# IambicKey.net
KiCad netlist of a schematic drawn in EAGLE
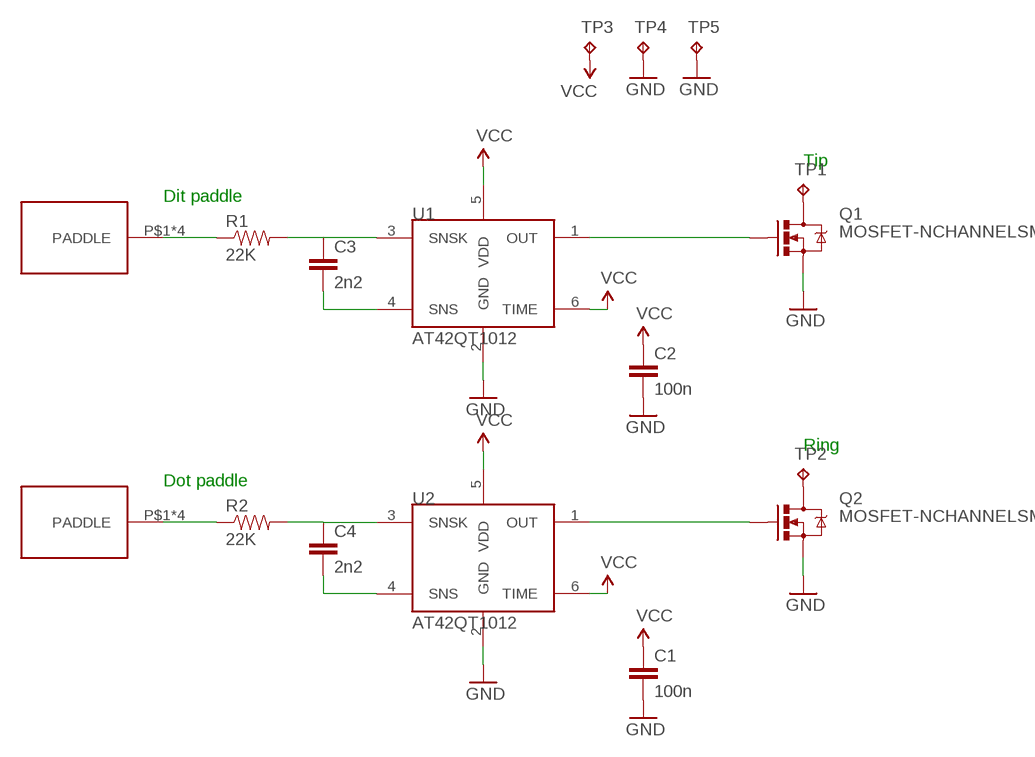
[diagram p0: schematic, sheet 1]

(export (version "E")
  (design (tool "Eeschema 10.0.6"))
  (components
    (comp (ref "C1")
      (value "100n")
      (footprint "eagle-import:0603-CAP")
      (libsource (lib "eagle-import") (part "CAP0603-CAP"))
    )
    (comp (ref "C2")
      (value "100n")
      (footprint "eagle-import:0603-CAP")
      (libsource (lib "eagle-import") (part "CAP0603-CAP"))
    )
    (comp (ref "C3")
      (value "2n2")
      (footprint "eagle-import:0603-CAP")
      (libsource (lib "eagle-import") (part "CAP0603-CAP"))
    )
    (comp (ref "C4")
      (value "2n2")
      (footprint "eagle-import:0603-CAP")
      (libsource (lib "eagle-import") (part "CAP0603-CAP"))
    )
    (comp (ref "Q1")
      (value "MOSFET-NCHANNELSMD")
      (footprint "eagle-import:SOT23-3")
      (libsource (lib "eagle-import") (part "MOSFET-NCHANNELSMD"))
    )
    (comp (ref "Q2")
      (value "MOSFET-NCHANNELSMD")
      (footprint "eagle-import:SOT23-3")
      (libsource (lib "eagle-import") (part "MOSFET-NCHANNELSMD"))
    )
    (comp (ref "R1")
      (value "22K")
      (footprint "eagle-import:0603-RES")
      (libsource (lib "eagle-import") (part "RESISTOR0603-RES"))
    )
    (comp (ref "R2")
      (value "22K")
      (footprint "eagle-import:0603-RES")
      (libsource (lib "eagle-import") (part "RESISTOR0603-RES"))
    )
    (comp (ref "TP1")
      (value "TPTP20SQ")
      (footprint "eagle-import:TP20SQ")
      (libsource (lib "eagle-import") (part "TPTP20SQ"))
    )
    (comp (ref "TP2")
      (value "TPTP20SQ")
      (footprint "eagle-import:TP20SQ")
      (libsource (lib "eagle-import") (part "TPTP20SQ"))
    )
    (comp (ref "TP3")
      (value "TPTP20SQ")
      (footprint "eagle-import:TP20SQ")
      (libsource (lib "eagle-import") (part "TPTP20SQ"))
    )
    (comp (ref "TP4")
      (value "TPTP20SQ")
      (footprint "eagle-import:TP20SQ")
      (libsource (lib "eagle-import") (part "TPTP20SQ"))
    )
    (comp (ref "TP5")
      (value "TPTP20SQ")
      (footprint "eagle-import:TP20SQ")
      (libsource (lib "eagle-import") (part "TPTP20SQ"))
    )
    (comp (ref "U$1")
      (value "PADDLE")
      (footprint "eagle-import:PADDLE")
      (libsource (lib "eagle-import") (part "PADDLE"))
    )
    (comp (ref "U$2")
      (value "PADDLE")
      (footprint "eagle-import:PADDLE")
      (libsource (lib "eagle-import") (part "PADDLE"))
    )
    (comp (ref "U1")
      (value "AT42QT1012")
      (footprint "eagle-import:SOT-23-6")
      (libsource (lib "eagle-import") (part "AT42QT1012"))
    )
    (comp (ref "U2")
      (value "AT42QT1012")
      (footprint "eagle-import:SOT-23-6")
      (libsource (lib "eagle-import") (part "AT42QT1012"))
    )
  )
  (nets
    (net (code "1") (name "GND") (class "Default")
      (node (ref "C1") (pin "2") (pinfunction "2_2") (pintype "passive"))
      (node (ref "C2") (pin "2") (pinfunction "2_2") (pintype "passive"))
      (node (ref "Q1") (pin "2") (pinfunction "S_2") (pintype "passive"))
      (node (ref "Q2") (pin "2") (pinfunction "S_2") (pintype "passive"))
      (node (ref "TP4") (pin "TP") (pinfunction "TP_TP") (pintype "input"))
      (node (ref "TP5") (pin "TP") (pinfunction "TP_TP") (pintype "input"))
      (node (ref "U1") (pin "2") (pinfunction "GND_2") (pintype "bidirectional"))
      (node (ref "U2") (pin "2") (pinfunction "GND_2") (pintype "bidirectional"))
    )
    (net (code "2") (name "Net-(Q1-D)") (class "Default")
      (node (ref "Q1") (pin "3") (pinfunction "D_3") (pintype "passive"))
      (node (ref "TP1") (pin "TP") (pinfunction "TP_TP") (pintype "input"))
    )
    (net (code "3") (name "Net-(Q1-G)") (class "Default")
      (node (ref "Q1") (pin "1") (pinfunction "G_1") (pintype "passive"))
      (node (ref "U1") (pin "1") (pinfunction "OUT_1") (pintype "bidirectional"))
    )
    (net (code "4") (name "Net-(Q2-D)") (class "Default")
      (node (ref "Q2") (pin "3") (pinfunction "D_3") (pintype "passive"))
      (node (ref "TP2") (pin "TP") (pinfunction "TP_TP") (pintype "input"))
    )
    (net (code "5") (name "Net-(Q2-G)") (class "Default")
      (node (ref "Q2") (pin "1") (pinfunction "G_1") (pintype "passive"))
      (node (ref "U2") (pin "1") (pinfunction "OUT_1") (pintype "bidirectional"))
    )
    (net (code "6") (name "Net-(R1-Pad1)") (class "Default")
      (node (ref "R1") (pin "1") (pinfunction "1_1") (pintype "passive"))
      (node (ref "U$1") (pin "P$1") (pinfunction "PADDLE_P$1") (pintype "bidirectional"))
      (node (ref "U$1") (pin "P$2") (pinfunction "PADDLE_P$2") (pintype "bidirectional"))
      (node (ref "U$1") (pin "P$3") (pinfunction "PADDLE_P$3") (pintype "bidirectional"))
      (node (ref "U$1") (pin "P$4") (pinfunction "PADDLE_P$4") (pintype "bidirectional"))
    )
    (net (code "7") (name "Net-(R2-Pad1)") (class "Default")
      (node (ref "R2") (pin "1") (pinfunction "1_1") (pintype "passive"))
      (node (ref "U$2") (pin "P$1") (pinfunction "PADDLE_P$1") (pintype "bidirectional"))
      (node (ref "U$2") (pin "P$2") (pinfunction "PADDLE_P$2") (pintype "bidirectional"))
      (node (ref "U$2") (pin "P$3") (pinfunction "PADDLE_P$3") (pintype "bidirectional"))
      (node (ref "U$2") (pin "P$4") (pinfunction "PADDLE_P$4") (pintype "bidirectional"))
    )
    (net (code "8") (name "Net-(U1-SNS)") (class "Default")
      (node (ref "C3") (pin "2") (pinfunction "2_2") (pintype "passive"))
      (node (ref "U1") (pin "4") (pinfunction "SNS_4") (pintype "bidirectional"))
    )
    (net (code "9") (name "Net-(U1-SNSK)") (class "Default")
      (node (ref "C3") (pin "1") (pinfunction "1_1") (pintype "passive"))
      (node (ref "R1") (pin "2") (pinfunction "2_2") (pintype "passive"))
      (node (ref "U1") (pin "3") (pinfunction "SNSK_3") (pintype "bidirectional"))
    )
    (net (code "10") (name "Net-(U2-SNS)") (class "Default")
      (node (ref "C4") (pin "2") (pinfunction "2_2") (pintype "passive"))
      (node (ref "U2") (pin "4") (pinfunction "SNS_4") (pintype "bidirectional"))
    )
    (net (code "11") (name "Net-(U2-SNSK)") (class "Default")
      (node (ref "C4") (pin "1") (pinfunction "1_1") (pintype "passive"))
      (node (ref "R2") (pin "2") (pinfunction "2_2") (pintype "passive"))
      (node (ref "U2") (pin "3") (pinfunction "SNSK_3") (pintype "bidirectional"))
    )
    (net (code "12") (name "VCC") (class "Default")
      (node (ref "C1") (pin "1") (pinfunction "1_1") (pintype "passive"))
      (node (ref "C2") (pin "1") (pinfunction "1_1") (pintype "passive"))
      (node (ref "TP3") (pin "TP") (pinfunction "TP_TP") (pintype "input"))
      (node (ref "U1") (pin "5") (pinfunction "VDD_5") (pintype "bidirectional"))
      (node (ref "U1") (pin "6") (pinfunction "TIME_6") (pintype "bidirectional"))
      (node (ref "U2") (pin "5") (pinfunction "VDD_5") (pintype "bidirectional"))
      (node (ref "U2") (pin "6") (pinfunction "TIME_6") (pintype "bidirectional"))
    )
  )
)
